# PSU_VCC1V0_FPGA_Buck.net
KiCad netlist of a schematic drawn in Altium Designer
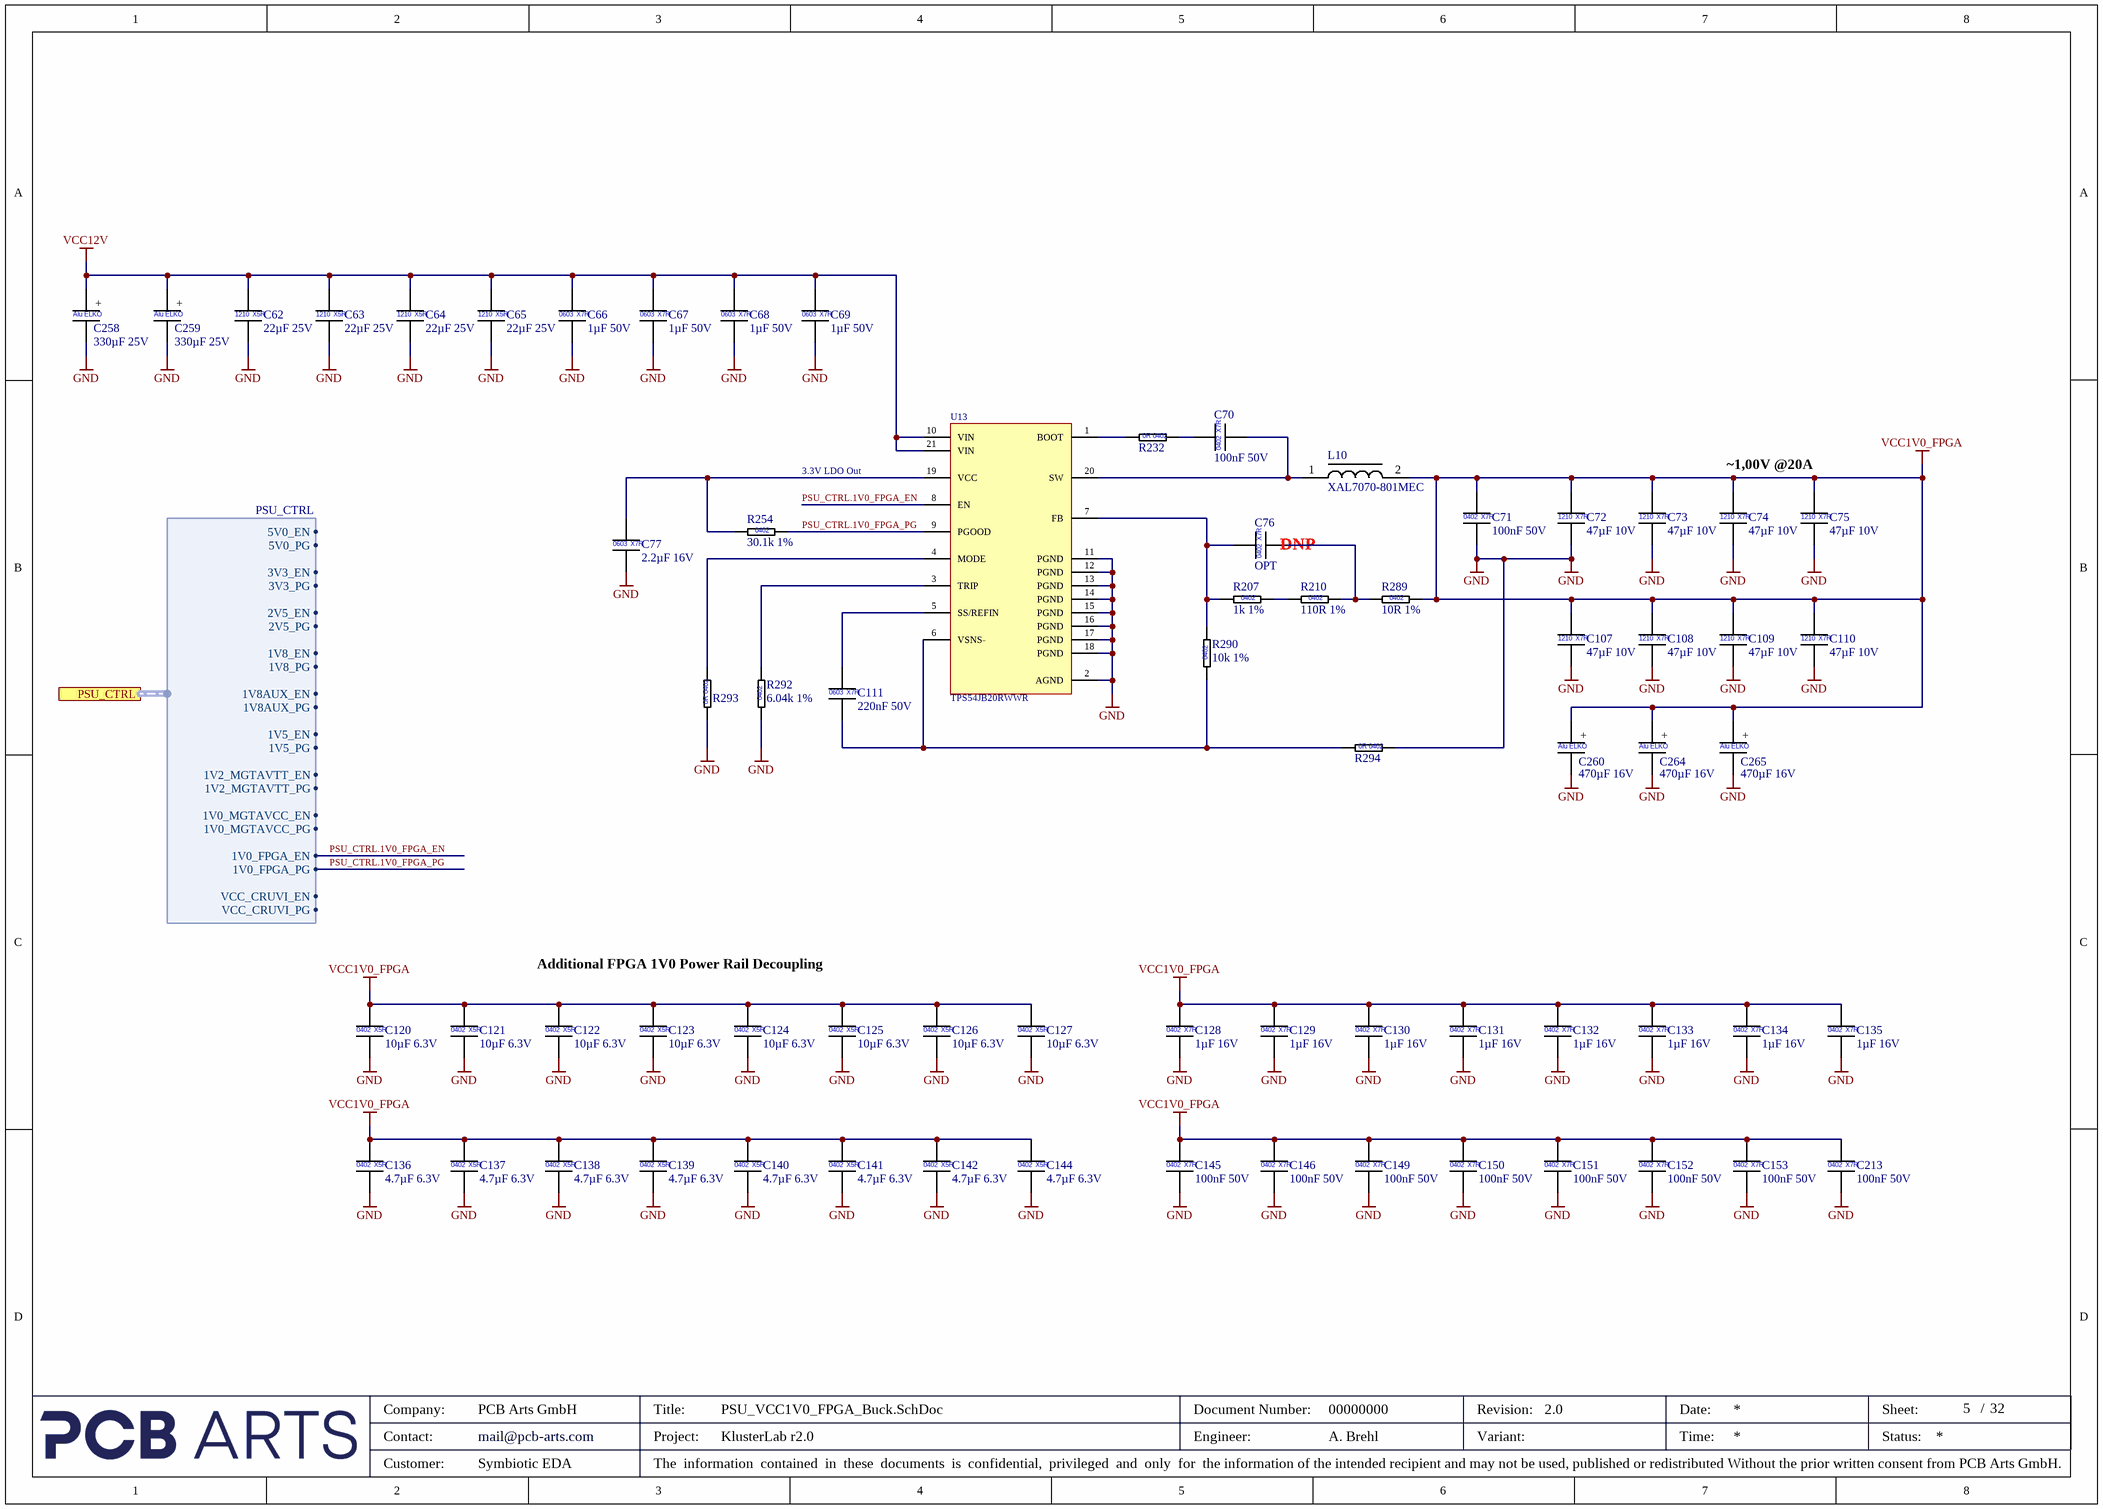
[diagram p0: PSU_VCC1V0_FPGA_Buck.SchDoc]

(export (version "E")
  (design (tool "Eeschema 10.0.6"))
  (components
    (comp (ref "C62")
      (value "22µF 25V")
      (footprint "Cap:CAP_1210")
      (description "Multilayer Ceramic Capacitors MLCC - SMD/SMT 1210 25VDC")
      (libsource (lib "Cap") (part "CAP_1210_22µF_25V"))
    )
    (comp (ref "C63")
      (value "22µF 25V")
      (footprint "Cap:CAP_1210")
      (description "Multilayer Ceramic Capacitors MLCC - SMD/SMT 1210 25VDC")
      (libsource (lib "Cap") (part "CAP_1210_22µF_25V"))
    )
    (comp (ref "C64")
      (value "22µF 25V")
      (footprint "Cap:CAP_1210")
      (description "Multilayer Ceramic Capacitors MLCC - SMD/SMT 1210 25VDC")
      (libsource (lib "Cap") (part "CAP_1210_22µF_25V"))
    )
    (comp (ref "C65")
      (value "22µF 25V")
      (footprint "Cap:CAP_1210")
      (description "Multilayer Ceramic Capacitors MLCC - SMD/SMT 1210 25VDC")
      (libsource (lib "Cap") (part "CAP_1210_22µF_25V"))
    )
    (comp (ref "C66")
      (value "1µF 50V")
      (footprint "CAP_0603")
      (description "Multilayer Ceramic Capacitors MLCC - SMD/SMT 50V 1uF X7R 0603 10%")
      (libsource (lib "Cap") (part "CAP_0603_1µF_50V_X7R_10%"))
    )
    (comp (ref "C67")
      (value "1µF 50V")
      (footprint "CAP_0603")
      (description "Multilayer Ceramic Capacitors MLCC - SMD/SMT 50V 1uF X7R 0603 10%")
      (libsource (lib "Cap") (part "CAP_0603_1µF_50V_X7R_10%"))
    )
    (comp (ref "C68")
      (value "1µF 50V")
      (footprint "CAP_0603")
      (description "Multilayer Ceramic Capacitors MLCC - SMD/SMT 50V 1uF X7R 0603 10%")
      (libsource (lib "Cap") (part "CAP_0603_1µF_50V_X7R_10%"))
    )
    (comp (ref "C69")
      (value "1µF 50V")
      (footprint "CAP_0603")
      (description "Multilayer Ceramic Capacitors MLCC - SMD/SMT 50V 1uF X7R 0603 10%")
      (libsource (lib "Cap") (part "CAP_0603_1µF_50V_X7R_10%"))
    )
    (comp (ref "C70")
      (value "100nF 50V")
      (footprint "Cap:CAP_0402")
      (description "Multilayer Ceramic Capacitors MLCC - SMD/SMT 0402 50VDC")
      (libsource (lib "Cap") (part "CAP_0402_100nF_50V"))
    )
    (comp (ref "C71")
      (value "100nF 50V")
      (footprint "Cap:CAP_0402")
      (description "Multilayer Ceramic Capacitors MLCC - SMD/SMT 0402 50VDC")
      (libsource (lib "") (part "CAP_0402_100nF_50V_1"))
    )
    (comp (ref "C72")
      (value "47µF 10V")
      (footprint "Cap:CAP_1210")
      (description "Multilayer Ceramic Capacitors MLCC - SMD/SMT 47 uF 10 VDC 10% 1210 X7R")
      (libsource (lib "Cap") (part "CAP_1210_47µF_10V_X7R_10%"))
    )
    (comp (ref "C73")
      (value "47µF 10V")
      (footprint "Cap:CAP_1210")
      (description "Multilayer Ceramic Capacitors MLCC - SMD/SMT 47 uF 10 VDC 10% 1210 X7R")
      (libsource (lib "Cap") (part "CAP_1210_47µF_10V_X7R_10%"))
    )
    (comp (ref "C74")
      (value "47µF 10V")
      (footprint "Cap:CAP_1210")
      (description "Multilayer Ceramic Capacitors MLCC - SMD/SMT 47 uF 10 VDC 10% 1210 X7R")
      (libsource (lib "Cap") (part "CAP_1210_47µF_10V_X7R_10%"))
    )
    (comp (ref "C75")
      (value "47µF 10V")
      (footprint "Cap:CAP_1210")
      (description "Multilayer Ceramic Capacitors MLCC - SMD/SMT 47 uF 10 VDC 10% 1210 X7R")
      (libsource (lib "Cap") (part "CAP_1210_47µF_10V_X7R_10%"))
    )
    (comp (ref "C76")
      (value "OPT")
      (footprint "Cap:CAP_0402")
      (description "Multilayer Ceramic Capacitors MLCC - SMD/SMT 0402 Optional Placeholder")
      (libsource (lib "Cap") (part "CAP_0402_OPT"))
    )
    (comp (ref "C77")
      (value "2.2µF 16V")
      (footprint "Cap:CAP_0603")
      (description "Multilayer Ceramic Capacitors MLCC - SMD/SMT 2.2 uF 16 VDC 10% 0603 X7R")
      (libsource (lib "Cap") (part "CAP_0603_2.2µF_16V_X7R_10%"))
    )
    (comp (ref "C107")
      (value "47µF 10V")
      (footprint "Cap:CAP_1210")
      (description "Multilayer Ceramic Capacitors MLCC - SMD/SMT 47 uF 10 VDC 10% 1210 X7R")
      (libsource (lib "Cap") (part "CAP_1210_47µF_10V_X7R_10%"))
    )
    (comp (ref "C108")
      (value "47µF 10V")
      (footprint "Cap:CAP_1210")
      (description "Multilayer Ceramic Capacitors MLCC - SMD/SMT 47 uF 10 VDC 10% 1210 X7R")
      (libsource (lib "Cap") (part "CAP_1210_47µF_10V_X7R_10%"))
    )
    (comp (ref "C109")
      (value "47µF 10V")
      (footprint "Cap:CAP_1210")
      (description "Multilayer Ceramic Capacitors MLCC - SMD/SMT 47 uF 10 VDC 10% 1210 X7R")
      (libsource (lib "Cap") (part "CAP_1210_47µF_10V_X7R_10%"))
    )
    (comp (ref "C110")
      (value "47µF 10V")
      (footprint "Cap:CAP_1210")
      (description "Multilayer Ceramic Capacitors MLCC - SMD/SMT 47 uF 10 VDC 10% 1210 X7R")
      (libsource (lib "Cap") (part "CAP_1210_47µF_10V_X7R_10%"))
    )
    (comp (ref "C111")
      (value "220nF 50V")
      (footprint "CAP_0603")
      (description "Multilayer Ceramic Capacitors MLCC - SMD/SMT 0.22 uF 50 VDC 10% 0603 X7R")
      (libsource (lib "Cap") (part "CAP_0603_220nF_50V_X7R_10%"))
    )
    (comp (ref "C120")
      (value "10µF 6.3V")
      (footprint "Cap:CAP_0402_L")
      (description "Multilayer Ceramic Capacitors MLCC - SMD/SMT 0402 6.3VDC")
      (libsource (lib "Cap") (part "CAP_0402_10µF_6.3V"))
    )
    (comp (ref "C121")
      (value "10µF 6.3V")
      (footprint "Cap:CAP_0402_L")
      (description "Multilayer Ceramic Capacitors MLCC - SMD/SMT 0402 6.3VDC")
      (libsource (lib "Cap") (part "CAP_0402_10µF_6.3V"))
    )
    (comp (ref "C122")
      (value "10µF 6.3V")
      (footprint "Cap:CAP_0402_L")
      (description "Multilayer Ceramic Capacitors MLCC - SMD/SMT 0402 6.3VDC")
      (libsource (lib "Cap") (part "CAP_0402_10µF_6.3V"))
    )
    (comp (ref "C123")
      (value "10µF 6.3V")
      (footprint "Cap:CAP_0402_L")
      (description "Multilayer Ceramic Capacitors MLCC - SMD/SMT 0402 6.3VDC")
      (libsource (lib "Cap") (part "CAP_0402_10µF_6.3V"))
    )
    (comp (ref "C124")
      (value "10µF 6.3V")
      (footprint "Cap:CAP_0402_L")
      (description "Multilayer Ceramic Capacitors MLCC - SMD/SMT 0402 6.3VDC")
      (libsource (lib "Cap") (part "CAP_0402_10µF_6.3V"))
    )
    (comp (ref "C125")
      (value "10µF 6.3V")
      (footprint "Cap:CAP_0402_L")
      (description "Multilayer Ceramic Capacitors MLCC - SMD/SMT 0402 6.3VDC")
      (libsource (lib "Cap") (part "CAP_0402_10µF_6.3V"))
    )
    (comp (ref "C126")
      (value "10µF 6.3V")
      (footprint "Cap:CAP_0402_L")
      (description "Multilayer Ceramic Capacitors MLCC - SMD/SMT 0402 6.3VDC")
      (libsource (lib "Cap") (part "CAP_0402_10µF_6.3V"))
    )
    (comp (ref "C127")
      (value "10µF 6.3V")
      (footprint "Cap:CAP_0402_L")
      (description "Multilayer Ceramic Capacitors MLCC - SMD/SMT 0402 6.3VDC")
      (libsource (lib "Cap") (part "CAP_0402_10µF_6.3V"))
    )
    (comp (ref "C128")
      (value "1µF 16V")
      (footprint "Cap:CAP_0402_L")
      (description "Multilayer Ceramic Capacitors MLCC - SMD/SMT 0402 16VDC")
      (libsource (lib "Cap") (part "CAP_0402_1µF_16V"))
    )
    (comp (ref "C129")
      (value "1µF 16V")
      (footprint "Cap:CAP_0402_L")
      (description "Multilayer Ceramic Capacitors MLCC - SMD/SMT 0402 16VDC")
      (libsource (lib "Cap") (part "CAP_0402_1µF_16V"))
    )
    (comp (ref "C130")
      (value "1µF 16V")
      (footprint "Cap:CAP_0402_L")
      (description "Multilayer Ceramic Capacitors MLCC - SMD/SMT 0402 16VDC")
      (libsource (lib "Cap") (part "CAP_0402_1µF_16V"))
    )
    (comp (ref "C131")
      (value "1µF 16V")
      (footprint "Cap:CAP_0402_L")
      (description "Multilayer Ceramic Capacitors MLCC - SMD/SMT 0402 16VDC")
      (libsource (lib "Cap") (part "CAP_0402_1µF_16V"))
    )
    (comp (ref "C132")
      (value "1µF 16V")
      (footprint "Cap:CAP_0402_L")
      (description "Multilayer Ceramic Capacitors MLCC - SMD/SMT 0402 16VDC")
      (libsource (lib "Cap") (part "CAP_0402_1µF_16V"))
    )
    (comp (ref "C133")
      (value "1µF 16V")
      (footprint "Cap:CAP_0402_L")
      (description "Multilayer Ceramic Capacitors MLCC - SMD/SMT 0402 16VDC")
      (libsource (lib "Cap") (part "CAP_0402_1µF_16V"))
    )
    (comp (ref "C134")
      (value "1µF 16V")
      (footprint "Cap:CAP_0402_L")
      (description "Multilayer Ceramic Capacitors MLCC - SMD/SMT 0402 16VDC")
      (libsource (lib "Cap") (part "CAP_0402_1µF_16V"))
    )
    (comp (ref "C135")
      (value "1µF 16V")
      (footprint "Cap:CAP_0402_L")
      (description "Multilayer Ceramic Capacitors MLCC - SMD/SMT 0402 16VDC")
      (libsource (lib "Cap") (part "CAP_0402_1µF_16V"))
    )
    (comp (ref "C136")
      (value "4.7µF 6.3V")
      (footprint "Cap:CAP_0402_L")
      (description "Multilayer Ceramic Capacitors MLCC - SMD/SMT 0402 6.3VDC")
      (libsource (lib "Cap") (part "CAP_0402_4.7µF_6.3V"))
    )
    (comp (ref "C137")
      (value "4.7µF 6.3V")
      (footprint "Cap:CAP_0402_L")
      (description "Multilayer Ceramic Capacitors MLCC - SMD/SMT 0402 6.3VDC")
      (libsource (lib "Cap") (part "CAP_0402_4.7µF_6.3V"))
    )
    (comp (ref "C138")
      (value "4.7µF 6.3V")
      (footprint "Cap:CAP_0402_L")
      (description "Multilayer Ceramic Capacitors MLCC - SMD/SMT 0402 6.3VDC")
      (libsource (lib "Cap") (part "CAP_0402_4.7µF_6.3V"))
    )
    (comp (ref "C139")
      (value "4.7µF 6.3V")
      (footprint "Cap:CAP_0402_L")
      (description "Multilayer Ceramic Capacitors MLCC - SMD/SMT 0402 6.3VDC")
      (libsource (lib "Cap") (part "CAP_0402_4.7µF_6.3V"))
    )
    (comp (ref "C140")
      (value "4.7µF 6.3V")
      (footprint "Cap:CAP_0402_L")
      (description "Multilayer Ceramic Capacitors MLCC - SMD/SMT 0402 6.3VDC")
      (libsource (lib "Cap") (part "CAP_0402_4.7µF_6.3V"))
    )
    (comp (ref "C141")
      (value "4.7µF 6.3V")
      (footprint "Cap:CAP_0402_L")
      (description "Multilayer Ceramic Capacitors MLCC - SMD/SMT 0402 6.3VDC")
      (libsource (lib "Cap") (part "CAP_0402_4.7µF_6.3V"))
    )
    (comp (ref "C142")
      (value "4.7µF 6.3V")
      (footprint "Cap:CAP_0402_L")
      (description "Multilayer Ceramic Capacitors MLCC - SMD/SMT 0402 6.3VDC")
      (libsource (lib "Cap") (part "CAP_0402_4.7µF_6.3V"))
    )
    (comp (ref "C144")
      (value "4.7µF 6.3V")
      (footprint "Cap:CAP_0402_L")
      (description "Multilayer Ceramic Capacitors MLCC - SMD/SMT 0402 6.3VDC")
      (libsource (lib "Cap") (part "CAP_0402_4.7µF_6.3V"))
    )
    (comp (ref "C145")
      (value "100nF 50V")
      (footprint "Cap:CAP_0402_L")
      (description "Multilayer Ceramic Capacitors MLCC - SMD/SMT 0402 50VDC")
      (libsource (lib "") (part "CAP_0402_100nF_50V_1"))
    )
    (comp (ref "C146")
      (value "100nF 50V")
      (footprint "Cap:CAP_0402_L")
      (description "Multilayer Ceramic Capacitors MLCC - SMD/SMT 0402 50VDC")
      (libsource (lib "") (part "CAP_0402_100nF_50V_1"))
    )
    (comp (ref "C149")
      (value "100nF 50V")
      (footprint "Cap:CAP_0402_L")
      (description "Multilayer Ceramic Capacitors MLCC - SMD/SMT 0402 50VDC")
      (libsource (lib "") (part "CAP_0402_100nF_50V_1"))
    )
    (comp (ref "C150")
      (value "100nF 50V")
      (footprint "Cap:CAP_0402_L")
      (description "Multilayer Ceramic Capacitors MLCC - SMD/SMT 0402 50VDC")
      (libsource (lib "") (part "CAP_0402_100nF_50V_1"))
    )
    (comp (ref "C151")
      (value "100nF 50V")
      (footprint "Cap:CAP_0402_L")
      (description "Multilayer Ceramic Capacitors MLCC - SMD/SMT 0402 50VDC")
      (libsource (lib "") (part "CAP_0402_100nF_50V_1"))
    )
    (comp (ref "C152")
      (value "100nF 50V")
      (footprint "Cap:CAP_0402_L")
      (description "Multilayer Ceramic Capacitors MLCC - SMD/SMT 0402 50VDC")
      (libsource (lib "") (part "CAP_0402_100nF_50V_1"))
    )
    (comp (ref "C153")
      (value "100nF 50V")
      (footprint "Cap:CAP_0402_L")
      (description "Multilayer Ceramic Capacitors MLCC - SMD/SMT 0402 50VDC")
      (libsource (lib "") (part "CAP_0402_100nF_50V_1"))
    )
    (comp (ref "C213")
      (value "100nF 50V")
      (footprint "Cap:CAP_0402_L")
      (description "Multilayer Ceramic Capacitors MLCC - SMD/SMT 0402 50VDC")
      (libsource (lib "") (part "CAP_0402_100nF_50V_1"))
    )
    (comp (ref "C258")
      (value "330µF 25V")
      (footprint "Cap:WCAP-PTG5_D10H12.5")
      (description "Organische Polymer-Aluminiumkondensatoren 330uF 25 Volts 20% AEC-Q200")
      (libsource (lib "Cap") (part "CAP_D10L12.5_330µF_25V"))
    )
    (comp (ref "C259")
      (value "330µF 25V")
      (footprint "Cap:WCAP-PTG5_D10H12.5")
      (description "Organische Polymer-Aluminiumkondensatoren 330uF 25 Volts 20% AEC-Q200")
      (libsource (lib "Cap") (part "CAP_D10L12.5_330µF_25V"))
    )
    (comp (ref "C260")
      (value "470µF 16V")
      (footprint "Cap:WCAP-PTG5_D8H13")
      (description "Organische Polymer-Aluminiumkondensatoren 470uF 16 Volts 20%")
      (libsource (lib "Cap") (part "CAP_D8L9_470µF_16V"))
    )
    (comp (ref "C264")
      (value "470µF 16V")
      (footprint "Cap:WCAP-PTG5_D8H13")
      (description "Organische Polymer-Aluminiumkondensatoren 470uF 16 Volts 20%")
      (libsource (lib "Cap") (part "CAP_D8L9_470µF_16V"))
    )
    (comp (ref "C265")
      (value "470µF 16V")
      (footprint "Cap:WCAP-PTG5_D8H13")
      (description "Organische Polymer-Aluminiumkondensatoren 470uF 16 Volts 20%")
      (libsource (lib "Cap") (part "CAP_D8L9_470µF_16V"))
    )
    (comp (ref "L10")
      (value "XAL7070-801MEC")
      (footprint "indc:COILCRAFT_XAL7070")
      (description "Power Inductors - SMD 800nH Shld 20% 25.8A 2.29mOhms AECQ200")
      (libsource (lib "Indc") (part "XAL7070-801MEC_Power Inductors SMD 800nH Shld 20% 25.8A 2.29mOhms AECQ200"))
    )
    (comp (ref "R207")
      (value "1k 1%")
      (footprint "res:RES_0402")
      (description "Thick Film Resistors - SMD 1kOhm 1%")
      (libsource (lib "Res") (part "RES_0402_1k_1%"))
    )
    (comp (ref "R210")
      (value "110R 1%")
      (footprint "res:RES_0402")
      (description "Thick Film Resistors - SMD 110Ohm 1%")
      (libsource (lib "Res") (part "RES_0402_110R_1%"))
    )
    (comp (ref "R232")
      (value "0R Jumper")
      (footprint "res:RES_0402")
      (description "Thick Film Resistors - SMD 0Ohm")
      (libsource (lib "Res") (part "RES_0402_0R Jumper"))
    )
    (comp (ref "R254")
      (value "30.1k 1%")
      (footprint "res:RES_0402")
      (description "Thick Film Resistors - SMD 30.1kOhm 1%")
      (libsource (lib "Res") (part "RES_0402_30.1k_1%"))
    )
    (comp (ref "R289")
      (value "10R 1%")
      (footprint "res:RES_0402")
      (description "Thick Film Resistors - SMD 10Ohm 1%")
      (libsource (lib "Res") (part "RES_0402_10R_1%"))
    )
    (comp (ref "R290")
      (value "10k 1%")
      (footprint "Res:RES_0402")
      (description "Thick Film Resistors - SMD 10kOhm 1%")
      (libsource (lib "Res") (part "RES_0402_10k_1%"))
    )
    (comp (ref "R292")
      (value "6.04k 1%")
      (footprint "Res:RES_0402")
      (description "Thick Film Resistors - SMD 6.04kOhm 1%")
      (libsource (lib "Res") (part "RES_0402_6.04k_1%"))
    )
    (comp (ref "R293")
      (value "0R Jumper")
      (footprint "res:RES_0402")
      (description "Thick Film Resistors - SMD 0Ohm")
      (libsource (lib "Res") (part "RES_0402_0R Jumper"))
    )
    (comp (ref "R294")
      (value "0R Jumper")
      (footprint "res:RES_0402")
      (description "Thick Film Resistors - SMD 0Ohm")
      (libsource (lib "Res") (part "RES_0402_0R Jumper"))
    )
    (comp (ref "U13")
      (value "TPS54JB20RWWR")
      (footprint "power:VQFN-HR21_RWW0021A")
      (description "Switching Voltage Regulators 2.7-V to 16-V input 20-A synchronous Buck")
      (libsource (lib "Power") (part "TPS54JB20RWWR_Switching Voltage Regulators 2.7-V to 16-V input 20-A synchronous Buck"))
    )
  )
  (nets
    (net (code "2") (name "/PSU_CTRL.1V0_FPGA_EN") (class "Default")
      (node (ref "U13") (pin "8") (pinfunction "EN_8") (pintype "passive"))
    )
    (net (code "3") (name "/PSU_CTRL.1V0_FPGA_PG") (class "Default")
      (node (ref "R254") (pin "2") (pinfunction "2_2") (pintype "passive"))
      (node (ref "U13") (pin "9") (pinfunction "PGOOD_9") (pintype "passive"))
    )
    (net (code "5") (name "GND") (class "Default")
      (node (ref "C107") (pin "2") (pinfunction "2_2") (pintype "passive"))
      (node (ref "C108") (pin "2") (pinfunction "2_2") (pintype "passive"))
      (node (ref "C109") (pin "2") (pinfunction "2_2") (pintype "passive"))
      (node (ref "C110") (pin "2") (pinfunction "2_2") (pintype "passive"))
      (node (ref "C120") (pin "2") (pinfunction "2_2") (pintype "passive"))
      (node (ref "C121") (pin "2") (pinfunction "2_2") (pintype "passive"))
      (node (ref "C122") (pin "2") (pinfunction "2_2") (pintype "passive"))
      (node (ref "C123") (pin "2") (pinfunction "2_2") (pintype "passive"))
      (node (ref "C124") (pin "2") (pinfunction "2_2") (pintype "passive"))
      (node (ref "C125") (pin "2") (pinfunction "2_2") (pintype "passive"))
      (node (ref "C126") (pin "2") (pinfunction "2_2") (pintype "passive"))
      (node (ref "C127") (pin "2") (pinfunction "2_2") (pintype "passive"))
      (node (ref "C128") (pin "2") (pinfunction "2_2") (pintype "passive"))
      (node (ref "C129") (pin "2") (pinfunction "2_2") (pintype "passive"))
      (node (ref "C130") (pin "2") (pinfunction "2_2") (pintype "passive"))
      (node (ref "C131") (pin "2") (pinfunction "2_2") (pintype "passive"))
      (node (ref "C132") (pin "2") (pinfunction "2_2") (pintype "passive"))
      (node (ref "C133") (pin "2") (pinfunction "2_2") (pintype "passive"))
      (node (ref "C134") (pin "2") (pinfunction "2_2") (pintype "passive"))
      (node (ref "C135") (pin "2") (pinfunction "2_2") (pintype "passive"))
      (node (ref "C136") (pin "2") (pinfunction "2_2") (pintype "passive"))
      (node (ref "C137") (pin "2") (pinfunction "2_2") (pintype "passive"))
      (node (ref "C138") (pin "2") (pinfunction "2_2") (pintype "passive"))
      (node (ref "C139") (pin "2") (pinfunction "2_2") (pintype "passive"))
      (node (ref "C140") (pin "2") (pinfunction "2_2") (pintype "passive"))
      (node (ref "C141") (pin "2") (pinfunction "2_2") (pintype "passive"))
      (node (ref "C142") (pin "2") (pinfunction "2_2") (pintype "passive"))
      (node (ref "C144") (pin "2") (pinfunction "2_2") (pintype "passive"))
      (node (ref "C145") (pin "2") (pinfunction "2_2") (pintype "passive"))
      (node (ref "C146") (pin "2") (pinfunction "2_2") (pintype "passive"))
      (node (ref "C149") (pin "2") (pinfunction "2_2") (pintype "passive"))
      (node (ref "C150") (pin "2") (pinfunction "2_2") (pintype "passive"))
      (node (ref "C151") (pin "2") (pinfunction "2_2") (pintype "passive"))
      (node (ref "C152") (pin "2") (pinfunction "2_2") (pintype "passive"))
      (node (ref "C153") (pin "2") (pinfunction "2_2") (pintype "passive"))
      (node (ref "C213") (pin "2") (pinfunction "2_2") (pintype "passive"))
      (node (ref "C258") (pin "2") (pinfunction "2_2") (pintype "passive"))
      (node (ref "C259") (pin "2") (pinfunction "2_2") (pintype "passive"))
      (node (ref "C260") (pin "2") (pinfunction "2_2") (pintype "passive"))
      (node (ref "C264") (pin "2") (pinfunction "2_2") (pintype "passive"))
      (node (ref "C265") (pin "2") (pinfunction "2_2") (pintype "passive"))
      (node (ref "C62") (pin "2") (pinfunction "2_2") (pintype "passive"))
      (node (ref "C63") (pin "2") (pinfunction "2_2") (pintype "passive"))
      (node (ref "C64") (pin "2") (pinfunction "2_2") (pintype "passive"))
      (node (ref "C65") (pin "2") (pinfunction "2_2") (pintype "passive"))
      (node (ref "C66") (pin "2") (pinfunction "2_2") (pintype "passive"))
      (node (ref "C67") (pin "2") (pinfunction "2_2") (pintype "passive"))
      (node (ref "C68") (pin "2") (pinfunction "2_2") (pintype "passive"))
      (node (ref "C69") (pin "2") (pinfunction "2_2") (pintype "passive"))
      (node (ref "C71") (pin "2") (pinfunction "2_2") (pintype "passive"))
      (node (ref "C72") (pin "2") (pinfunction "2_2") (pintype "passive"))
      (node (ref "C73") (pin "2") (pinfunction "2_2") (pintype "passive"))
      (node (ref "C74") (pin "2") (pinfunction "2_2") (pintype "passive"))
      (node (ref "C75") (pin "2") (pinfunction "2_2") (pintype "passive"))
      (node (ref "C77") (pin "2") (pinfunction "2_2") (pintype "passive"))
      (node (ref "R292") (pin "1") (pinfunction "1_1") (pintype "passive"))
      (node (ref "R293") (pin "1") (pinfunction "1_1") (pintype "passive"))
      (node (ref "R294") (pin "2") (pinfunction "2_2") (pintype "passive"))
      (node (ref "U13") (pin "11") (pinfunction "PGND_11") (pintype "passive"))
      (node (ref "U13") (pin "12") (pinfunction "PGND_12") (pintype "passive"))
      (node (ref "U13") (pin "13") (pinfunction "PGND_13") (pintype "passive"))
      (node (ref "U13") (pin "14") (pinfunction "PGND_14") (pintype "passive"))
      (node (ref "U13") (pin "15") (pinfunction "PGND_15") (pintype "passive"))
      (node (ref "U13") (pin "16") (pinfunction "PGND_16") (pintype "passive"))
      (node (ref "U13") (pin "17") (pinfunction "PGND_17") (pintype "passive"))
      (node (ref "U13") (pin "18") (pinfunction "PGND_18") (pintype "passive"))
      (node (ref "U13") (pin "2") (pinfunction "AGND_2") (pintype "passive"))
    )
    (net (code "6") (name "Net-(C70-Pad1)") (class "Default")
      (node (ref "C70") (pin "1") (pinfunction "1_1") (pintype "passive"))
      (node (ref "R232") (pin "2") (pinfunction "2_2") (pintype "passive"))
    )
    (net (code "7") (name "Net-(C76-Pad2)") (class "Default")
      (node (ref "C76") (pin "2") (pinfunction "2_2") (pintype "passive"))
      (node (ref "R210") (pin "2") (pinfunction "2_2") (pintype "passive"))
      (node (ref "R289") (pin "1") (pinfunction "1_1") (pintype "passive"))
    )
    (net (code "8") (name "Net-(R207-Pad2)") (class "Default")
      (node (ref "R207") (pin "2") (pinfunction "2_2") (pintype "passive"))
      (node (ref "R210") (pin "1") (pinfunction "1_1") (pintype "passive"))
    )
    (net (code "9") (name "Net-(U13-BOOT)") (class "Default")
      (node (ref "R232") (pin "1") (pinfunction "1_1") (pintype "passive"))
      (node (ref "U13") (pin "1") (pinfunction "BOOT_1") (pintype "passive"))
    )
    (net (code "10") (name "Net-(U13-FB)") (class "Default")
      (node (ref "C76") (pin "1") (pinfunction "1_1") (pintype "passive"))
      (node (ref "R207") (pin "1") (pinfunction "1_1") (pintype "passive"))
      (node (ref "R290") (pin "2") (pinfunction "2_2") (pintype "passive"))
      (node (ref "U13") (pin "7") (pinfunction "FB_7") (pintype "passive"))
    )
    (net (code "11") (name "Net-(U13-MODE)") (class "Default")
      (node (ref "R293") (pin "2") (pinfunction "2_2") (pintype "passive"))
      (node (ref "U13") (pin "4") (pinfunction "MODE_4") (pintype "passive"))
    )
    (net (code "12") (name "Net-(U13-SS{slash}REFIN)") (class "Default")
      (node (ref "C111") (pin "1") (pinfunction "1_1") (pintype "passive"))
      (node (ref "U13") (pin "5") (pinfunction "SS/REFIN_5") (pintype "passive"))
    )
    (net (code "13") (name "Net-(U13-SW)") (class "Default")
      (node (ref "C70") (pin "2") (pinfunction "2_2") (pintype "passive"))
      (node (ref "L10") (pin "1") (pinfunction "1_1") (pintype "passive"))
      (node (ref "U13") (pin "20") (pinfunction "SW_20") (pintype "passive"))
    )
    (net (code "14") (name "Net-(U13-TRIP)") (class "Default")
      (node (ref "R292") (pin "2") (pinfunction "2_2") (pintype "passive"))
      (node (ref "U13") (pin "3") (pinfunction "TRIP_3") (pintype "passive"))
    )
    (net (code "15") (name "Net-(U13-VCC)") (class "Default")
      (node (ref "C77") (pin "1") (pinfunction "1_1") (pintype "passive"))
      (node (ref "R254") (pin "1") (pinfunction "1_1") (pintype "passive"))
      (node (ref "U13") (pin "19") (pinfunction "VCC_19") (pintype "passive"))
    )
    (net (code "16") (name "Net-(U13-VSNS-)") (class "Default")
      (node (ref "C111") (pin "2") (pinfunction "2_2") (pintype "passive"))
      (node (ref "R290") (pin "1") (pinfunction "1_1") (pintype "passive"))
      (node (ref "R294") (pin "1") (pinfunction "1_1") (pintype "passive"))
      (node (ref "U13") (pin "6") (pinfunction "VSNS-_6") (pintype "passive"))
    )
    (net (code "17") (name "VCC1V0_FPGA") (class "Default")
      (node (ref "C107") (pin "1") (pinfunction "1_1") (pintype "passive"))
      (node (ref "C108") (pin "1") (pinfunction "1_1") (pintype "passive"))
      (node (ref "C109") (pin "1") (pinfunction "1_1") (pintype "passive"))
      (node (ref "C110") (pin "1") (pinfunction "1_1") (pintype "passive"))
      (node (ref "C120") (pin "1") (pinfunction "1_1") (pintype "passive"))
      (node (ref "C121") (pin "1") (pinfunction "1_1") (pintype "passive"))
      (node (ref "C122") (pin "1") (pinfunction "1_1") (pintype "passive"))
      (node (ref "C123") (pin "1") (pinfunction "1_1") (pintype "passive"))
      (node (ref "C124") (pin "1") (pinfunction "1_1") (pintype "passive"))
      (node (ref "C125") (pin "1") (pinfunction "1_1") (pintype "passive"))
      (node (ref "C126") (pin "1") (pinfunction "1_1") (pintype "passive"))
      (node (ref "C127") (pin "1") (pinfunction "1_1") (pintype "passive"))
      (node (ref "C128") (pin "1") (pinfunction "1_1") (pintype "passive"))
      (node (ref "C129") (pin "1") (pinfunction "1_1") (pintype "passive"))
      (node (ref "C130") (pin "1") (pinfunction "1_1") (pintype "passive"))
      (node (ref "C131") (pin "1") (pinfunction "1_1") (pintype "passive"))
      (node (ref "C132") (pin "1") (pinfunction "1_1") (pintype "passive"))
      (node (ref "C133") (pin "1") (pinfunction "1_1") (pintype "passive"))
      (node (ref "C134") (pin "1") (pinfunction "1_1") (pintype "passive"))
      (node (ref "C135") (pin "1") (pinfunction "1_1") (pintype "passive"))
      (node (ref "C136") (pin "1") (pinfunction "1_1") (pintype "passive"))
      (node (ref "C137") (pin "1") (pinfunction "1_1") (pintype "passive"))
      (node (ref "C138") (pin "1") (pinfunction "1_1") (pintype "passive"))
      (node (ref "C139") (pin "1") (pinfunction "1_1") (pintype "passive"))
      (node (ref "C140") (pin "1") (pinfunction "1_1") (pintype "passive"))
      (node (ref "C141") (pin "1") (pinfunction "1_1") (pintype "passive"))
      (node (ref "C142") (pin "1") (pinfunction "1_1") (pintype "passive"))
      (node (ref "C144") (pin "1") (pinfunction "1_1") (pintype "passive"))
      (node (ref "C145") (pin "1") (pinfunction "1_1") (pintype "passive"))
      (node (ref "C146") (pin "1") (pinfunction "1_1") (pintype "passive"))
      (node (ref "C149") (pin "1") (pinfunction "1_1") (pintype "passive"))
      (node (ref "C150") (pin "1") (pinfunction "1_1") (pintype "passive"))
      (node (ref "C151") (pin "1") (pinfunction "1_1") (pintype "passive"))
      (node (ref "C152") (pin "1") (pinfunction "1_1") (pintype "passive"))
      (node (ref "C153") (pin "1") (pinfunction "1_1") (pintype "passive"))
      (node (ref "C213") (pin "1") (pinfunction "1_1") (pintype "passive"))
      (node (ref "C260") (pin "1") (pinfunction "1_1") (pintype "passive"))
      (node (ref "C264") (pin "1") (pinfunction "1_1") (pintype "passive"))
      (node (ref "C265") (pin "1") (pinfunction "1_1") (pintype "passive"))
      (node (ref "C71") (pin "1") (pinfunction "1_1") (pintype "passive"))
      (node (ref "C72") (pin "1") (pinfunction "1_1") (pintype "passive"))
      (node (ref "C73") (pin "1") (pinfunction "1_1") (pintype "passive"))
      (node (ref "C74") (pin "1") (pinfunction "1_1") (pintype "passive"))
      (node (ref "C75") (pin "1") (pinfunction "1_1") (pintype "passive"))
      (node (ref "L10") (pin "2") (pinfunction "2_2") (pintype "passive"))
      (node (ref "R289") (pin "2") (pinfunction "2_2") (pintype "passive"))
    )
    (net (code "18") (name "VCC12V") (class "Default")
      (node (ref "C258") (pin "1") (pinfunction "1_1") (pintype "passive"))
      (node (ref "C259") (pin "1") (pinfunction "1_1") (pintype "passive"))
      (node (ref "C62") (pin "1") (pinfunction "1_1") (pintype "passive"))
      (node (ref "C63") (pin "1") (pinfunction "1_1") (pintype "passive"))
      (node (ref "C64") (pin "1") (pinfunction "1_1") (pintype "passive"))
      (node (ref "C65") (pin "1") (pinfunction "1_1") (pintype "passive"))
      (node (ref "C66") (pin "1") (pinfunction "1_1") (pintype "passive"))
      (node (ref "C67") (pin "1") (pinfunction "1_1") (pintype "passive"))
      (node (ref "C68") (pin "1") (pinfunction "1_1") (pintype "passive"))
      (node (ref "C69") (pin "1") (pinfunction "1_1") (pintype "passive"))
      (node (ref "U13") (pin "10") (pinfunction "VIN_10") (pintype "passive"))
      (node (ref "U13") (pin "21") (pinfunction "VIN_21") (pintype "passive"))
    )
  )
)
